# Coatroller.net
KiCad netlist of a schematic drawn in EAGLE
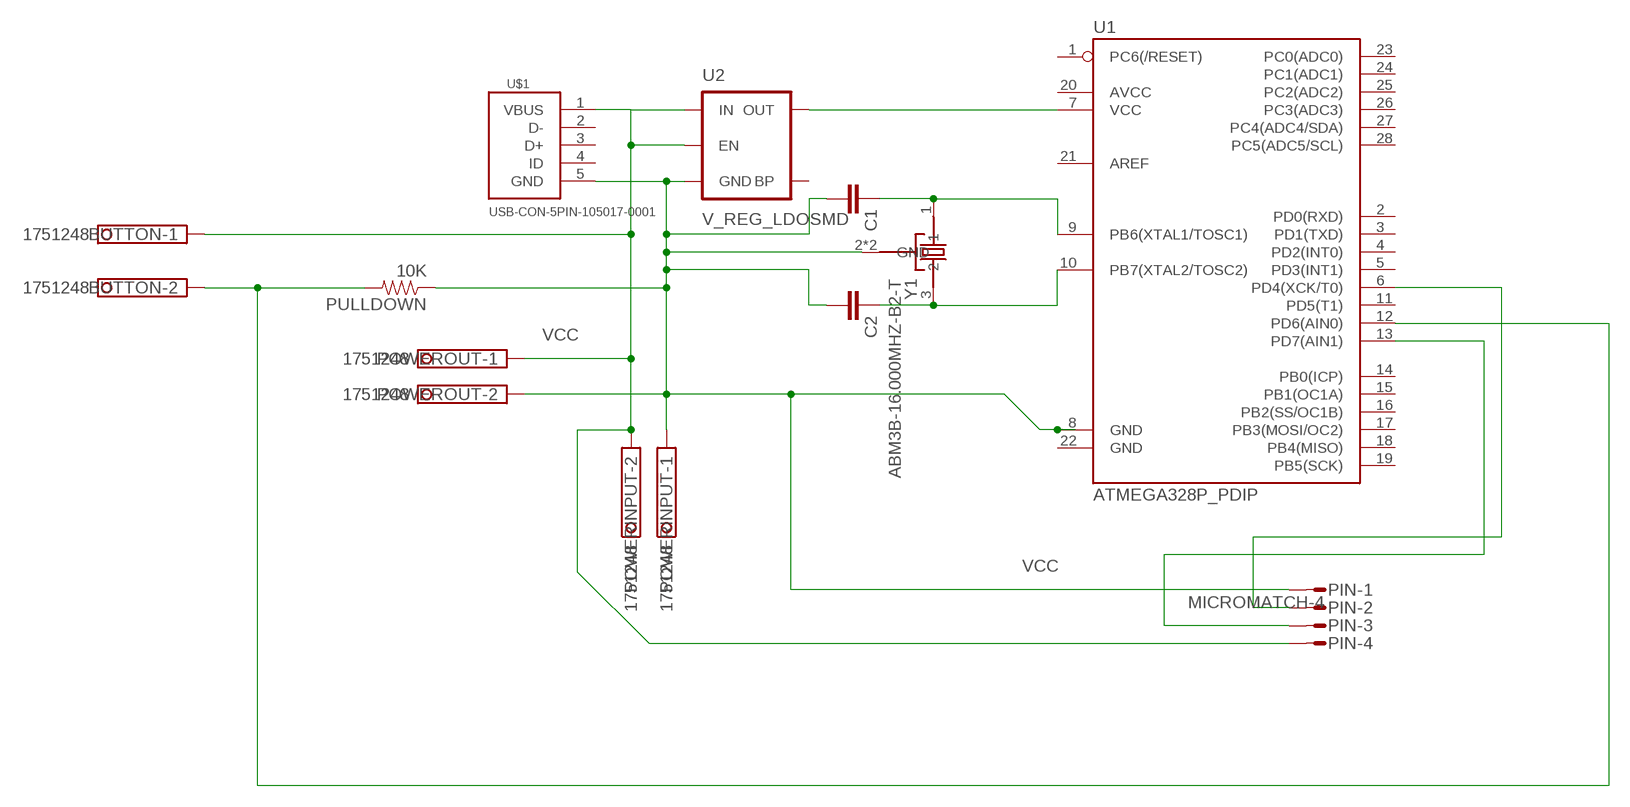
[diagram p0: schematic, sheet 1]

(export (version "E")
  (design (tool "Eeschema 10.0.6"))
  (components
    (comp (ref "BUTTON")
      (value "1751248")
      (footprint "eagle-import:1751248")
      (libsource (lib "eagle-import") (part "1751248"))
    )
    (comp (ref "C1")
      (value "2.2UF50V10%(1206)")
      (footprint "eagle-import:1206-CAP")
      (libsource (lib "eagle-import") (part "2.2UF50V10%(1206)"))
    )
    (comp (ref "C2")
      (value "2.2UF50V10%(1206)")
      (footprint "eagle-import:1206-CAP")
      (libsource (lib "eagle-import") (part "2.2UF50V10%(1206)"))
    )
    (comp (ref "PIN")
      (value "MICROMATCH-4")
      (footprint "eagle-import:MICROMATCH-4")
      (fields (field (name "MPN") "7-215464-4"))
      (libsource (lib "eagle-import") (part "MICROMATCH-4"))
    )
    (comp (ref "POWERINPUT")
      (value "1751248")
      (footprint "eagle-import:1751248")
      (libsource (lib "eagle-import") (part "1751248"))
    )
    (comp (ref "POWEROUT")
      (value "1751248")
      (footprint "eagle-import:1751248")
      (libsource (lib "eagle-import") (part "1751248"))
    )
    (comp (ref "PULLDOWN")
      (value "10K")
      (footprint "eagle-import:0603-RES")
      (libsource (lib "eagle-import") (part "10KOHM-1/10W-1%(0603)0603"))
    )
    (comp (ref "U$1")
      (value "USB-CON-5PIN-105017-0001")
      (footprint "eagle-import:USB-MICRO-MOLEX-105017-0001")
      (libsource (lib "eagle-import") (part "USB-CON-5PIN-105017-0001"))
    )
    (comp (ref "U1")
      (value "ATMEGA328P_PDIP")
      (footprint "eagle-import:DIL28-3")
      (libsource (lib "eagle-import") (part "ATMEGA328P_PDIP"))
    )
    (comp (ref "U2")
      (value "V_REG_LDOSMD")
      (footprint "eagle-import:SOT23-5")
      (libsource (lib "eagle-import") (part "V_REG_LDOSMD"))
    )
    (comp (ref "Y1")
      (value "ABM3B-16.000MHZ-B2-T")
      (footprint "eagle-import:OSCSC500X320X110-4N")
      (fields (field (name "MF") "Abracon"))
      (libsource (lib "eagle-import") (part "ABM3B-16.000MHZ-B2-T"))
    )
  )
  (nets
    (net (code "1") (name "/VCC") (class "Default")
      (node (ref "BUTTON") (pin "1") (pinfunction "K_1") (pintype "passive"))
      (node (ref "PIN") (pin "4") (pinfunction "S_4") (pintype "passive"))
      (node (ref "POWERINPUT") (pin "2") (pinfunction "K_2") (pintype "passive"))
      (node (ref "POWEROUT") (pin "1") (pinfunction "K_1") (pintype "passive"))
      (node (ref "U$1") (pin "1") (pinfunction "VBUS_1") (pintype "power_in"))
      (node (ref "U2") (pin "1") (pinfunction "IN_1") (pintype "input"))
      (node (ref "U2") (pin "3") (pinfunction "EN_3") (pintype "input"))
    )
    (net (code "2") (name "Net-(BUTTONB-K)") (class "Default")
      (node (ref "BUTTON") (pin "2") (pinfunction "K_2") (pintype "passive"))
      (node (ref "PULLDOWN") (pin "2") (pinfunction "2_2") (pintype "passive"))
      (node (ref "U1") (pin "12") (pinfunction "PD6(AIN0)_12") (pintype "bidirectional"))
    )
    (net (code "3") (name "Net-(PINA-S)") (class "Default")
      (node (ref "C1") (pin "2") (pinfunction "2_2") (pintype "passive"))
      (node (ref "C2") (pin "2") (pinfunction "2_2") (pintype "passive"))
      (node (ref "PIN") (pin "1") (pinfunction "S_1") (pintype "passive"))
      (node (ref "POWERINPUT") (pin "1") (pinfunction "K_1") (pintype "passive"))
      (node (ref "POWEROUT") (pin "2") (pinfunction "K_2") (pintype "passive"))
      (node (ref "PULLDOWN") (pin "1") (pinfunction "1_1") (pintype "passive"))
      (node (ref "U$1") (pin "5") (pinfunction "GND_5") (pintype "power_in"))
      (node (ref "U1") (pin "8") (pinfunction "GND_8") (pintype "bidirectional"))
      (node (ref "U2") (pin "2") (pinfunction "GND_2") (pintype "input"))
      (node (ref "Y1") (pin "2") (pinfunction "GND_2") (pintype "passive"))
      (node (ref "Y1") (pin "4") (pinfunction "GND_4") (pintype "passive"))
    )
    (net (code "4") (name "Net-(PINB-S)") (class "Default")
      (node (ref "PIN") (pin "2") (pinfunction "S_2") (pintype "passive"))
      (node (ref "U1") (pin "6") (pinfunction "PD4(XCK/T0)_6") (pintype "bidirectional"))
    )
    (net (code "5") (name "Net-(PINC-S)") (class "Default")
      (node (ref "PIN") (pin "3") (pinfunction "S_3") (pintype "passive"))
      (node (ref "U1") (pin "13") (pinfunction "PD7(AIN1)_13") (pintype "bidirectional"))
    )
    (net (code "6") (name "Net-(U1-PB6(XTAL1{slash}TOSC1))") (class "Default")
      (node (ref "C1") (pin "1") (pinfunction "1_1") (pintype "passive"))
      (node (ref "U1") (pin "9") (pinfunction "PB6(XTAL1/TOSC1)_9") (pintype "bidirectional"))
      (node (ref "Y1") (pin "1") (pinfunction "1_1") (pintype "passive"))
    )
    (net (code "7") (name "Net-(U1-PB7(XTAL2{slash}TOSC2))") (class "Default")
      (node (ref "C2") (pin "1") (pinfunction "1_1") (pintype "passive"))
      (node (ref "U1") (pin "10") (pinfunction "PB7(XTAL2/TOSC2)_10") (pintype "bidirectional"))
      (node (ref "Y1") (pin "3") (pinfunction "2_3") (pintype "passive"))
    )
    (net (code "8") (name "Net-(U1-VCC)") (class "Default")
      (node (ref "U1") (pin "7") (pinfunction "VCC_7") (pintype "bidirectional"))
      (node (ref "U2") (pin "5") (pinfunction "OUT_5") (pintype "passive"))
    )
    (net (code "9") (name "unconnected-(U$1-D+-Pad3)") (class "Default")
      (node (ref "U$1") (pin "3") (pinfunction "D+_3") (pintype "bidirectional"))
    )
    (net (code "10") (name "unconnected-(U$1-D--Pad2)") (class "Default")
      (node (ref "U$1") (pin "2") (pinfunction "D-_2") (pintype "bidirectional"))
    )
    (net (code "11") (name "unconnected-(U$1-ID-Pad4)") (class "Default")
      (node (ref "U$1") (pin "4") (pinfunction "ID_4") (pintype "bidirectional"))
    )
    (net (code "12") (name "unconnected-(U1-AREF-Pad21)") (class "Default")
      (node (ref "U1") (pin "21") (pinfunction "AREF_21") (pintype "bidirectional"))
    )
    (net (code "13") (name "unconnected-(U1-AVCC-Pad20)") (class "Default")
      (node (ref "U1") (pin "20") (pinfunction "AVCC_20") (pintype "bidirectional"))
    )
    (net (code "14") (name "unconnected-(U1-GND-Pad22)") (class "Default")
      (node (ref "U1") (pin "22") (pinfunction "GND_22") (pintype "bidirectional"))
    )
    (net (code "15") (name "unconnected-(U1-PB0(ICP)-Pad14)") (class "Default")
      (node (ref "U1") (pin "14") (pinfunction "PB0(ICP)_14") (pintype "bidirectional"))
    )
    (net (code "16") (name "unconnected-(U1-PB1(OC1A)-Pad15)") (class "Default")
      (node (ref "U1") (pin "15") (pinfunction "PB1(OC1A)_15") (pintype "bidirectional"))
    )
    (net (code "17") (name "unconnected-(U1-PB2(SS{slash}OC1B)-Pad16)") (class "Default")
      (node (ref "U1") (pin "16") (pinfunction "PB2(SS/OC1B)_16") (pintype "bidirectional"))
    )
    (net (code "18") (name "unconnected-(U1-PB3(MOSI{slash}OC2)-Pad17)") (class "Default")
      (node (ref "U1") (pin "17") (pinfunction "PB3(MOSI/OC2)_17") (pintype "bidirectional"))
    )
    (net (code "19") (name "unconnected-(U1-PB4(MISO)-Pad18)") (class "Default")
      (node (ref "U1") (pin "18") (pinfunction "PB4(MISO)_18") (pintype "bidirectional"))
    )
    (net (code "20") (name "unconnected-(U1-PB5(SCK)-Pad19)") (class "Default")
      (node (ref "U1") (pin "19") (pinfunction "PB5(SCK)_19") (pintype "bidirectional"))
    )
    (net (code "21") (name "unconnected-(U1-PC0(ADC0)-Pad23)") (class "Default")
      (node (ref "U1") (pin "23") (pinfunction "PC0(ADC0)_23") (pintype "bidirectional"))
    )
    (net (code "22") (name "unconnected-(U1-PC1(ADC1)-Pad24)") (class "Default")
      (node (ref "U1") (pin "24") (pinfunction "PC1(ADC1)_24") (pintype "bidirectional"))
    )
    (net (code "23") (name "unconnected-(U1-PC2(ADC2)-Pad25)") (class "Default")
      (node (ref "U1") (pin "25") (pinfunction "PC2(ADC2)_25") (pintype "bidirectional"))
    )
    (net (code "24") (name "unconnected-(U1-PC3(ADC3)-Pad26)") (class "Default")
      (node (ref "U1") (pin "26") (pinfunction "PC3(ADC3)_26") (pintype "bidirectional"))
    )
    (net (code "25") (name "unconnected-(U1-PC4(ADC4{slash}SDA)-Pad27)") (class "Default")
      (node (ref "U1") (pin "27") (pinfunction "PC4(ADC4/SDA)_27") (pintype "bidirectional"))
    )
    (net (code "26") (name "unconnected-(U1-PC5(ADC5{slash}SCL)-Pad28)") (class "Default")
      (node (ref "U1") (pin "28") (pinfunction "PC5(ADC5/SCL)_28") (pintype "bidirectional"))
    )
    (net (code "27") (name "unconnected-(U1-PC6({slash}RESET)-Pad1)") (class "Default")
      (node (ref "U1") (pin "1") (pinfunction "PC6(/RESET)_1") (pintype "bidirectional"))
    )
    (net (code "28") (name "unconnected-(U1-PD0(RXD)-Pad2)") (class "Default")
      (node (ref "U1") (pin "2") (pinfunction "PD0(RXD)_2") (pintype "bidirectional"))
    )
    (net (code "29") (name "unconnected-(U1-PD1(TXD)-Pad3)") (class "Default")
      (node (ref "U1") (pin "3") (pinfunction "PD1(TXD)_3") (pintype "bidirectional"))
    )
    (net (code "30") (name "unconnected-(U1-PD2(INT0)-Pad4)") (class "Default")
      (node (ref "U1") (pin "4") (pinfunction "PD2(INT0)_4") (pintype "bidirectional"))
    )
    (net (code "31") (name "unconnected-(U1-PD3(INT1)-Pad5)") (class "Default")
      (node (ref "U1") (pin "5") (pinfunction "PD3(INT1)_5") (pintype "bidirectional"))
    )
    (net (code "32") (name "unconnected-(U1-PD5(T1)-Pad11)") (class "Default")
      (node (ref "U1") (pin "11") (pinfunction "PD5(T1)_11") (pintype "bidirectional"))
    )
    (net (code "33") (name "unconnected-(U2-BP-Pad4)") (class "Default")
      (node (ref "U2") (pin "4") (pinfunction "BP_4") (pintype "input"))
    )
  )
)
